# VierGewinnt010.net
KiCad netlist of a schematic drawn in EAGLE
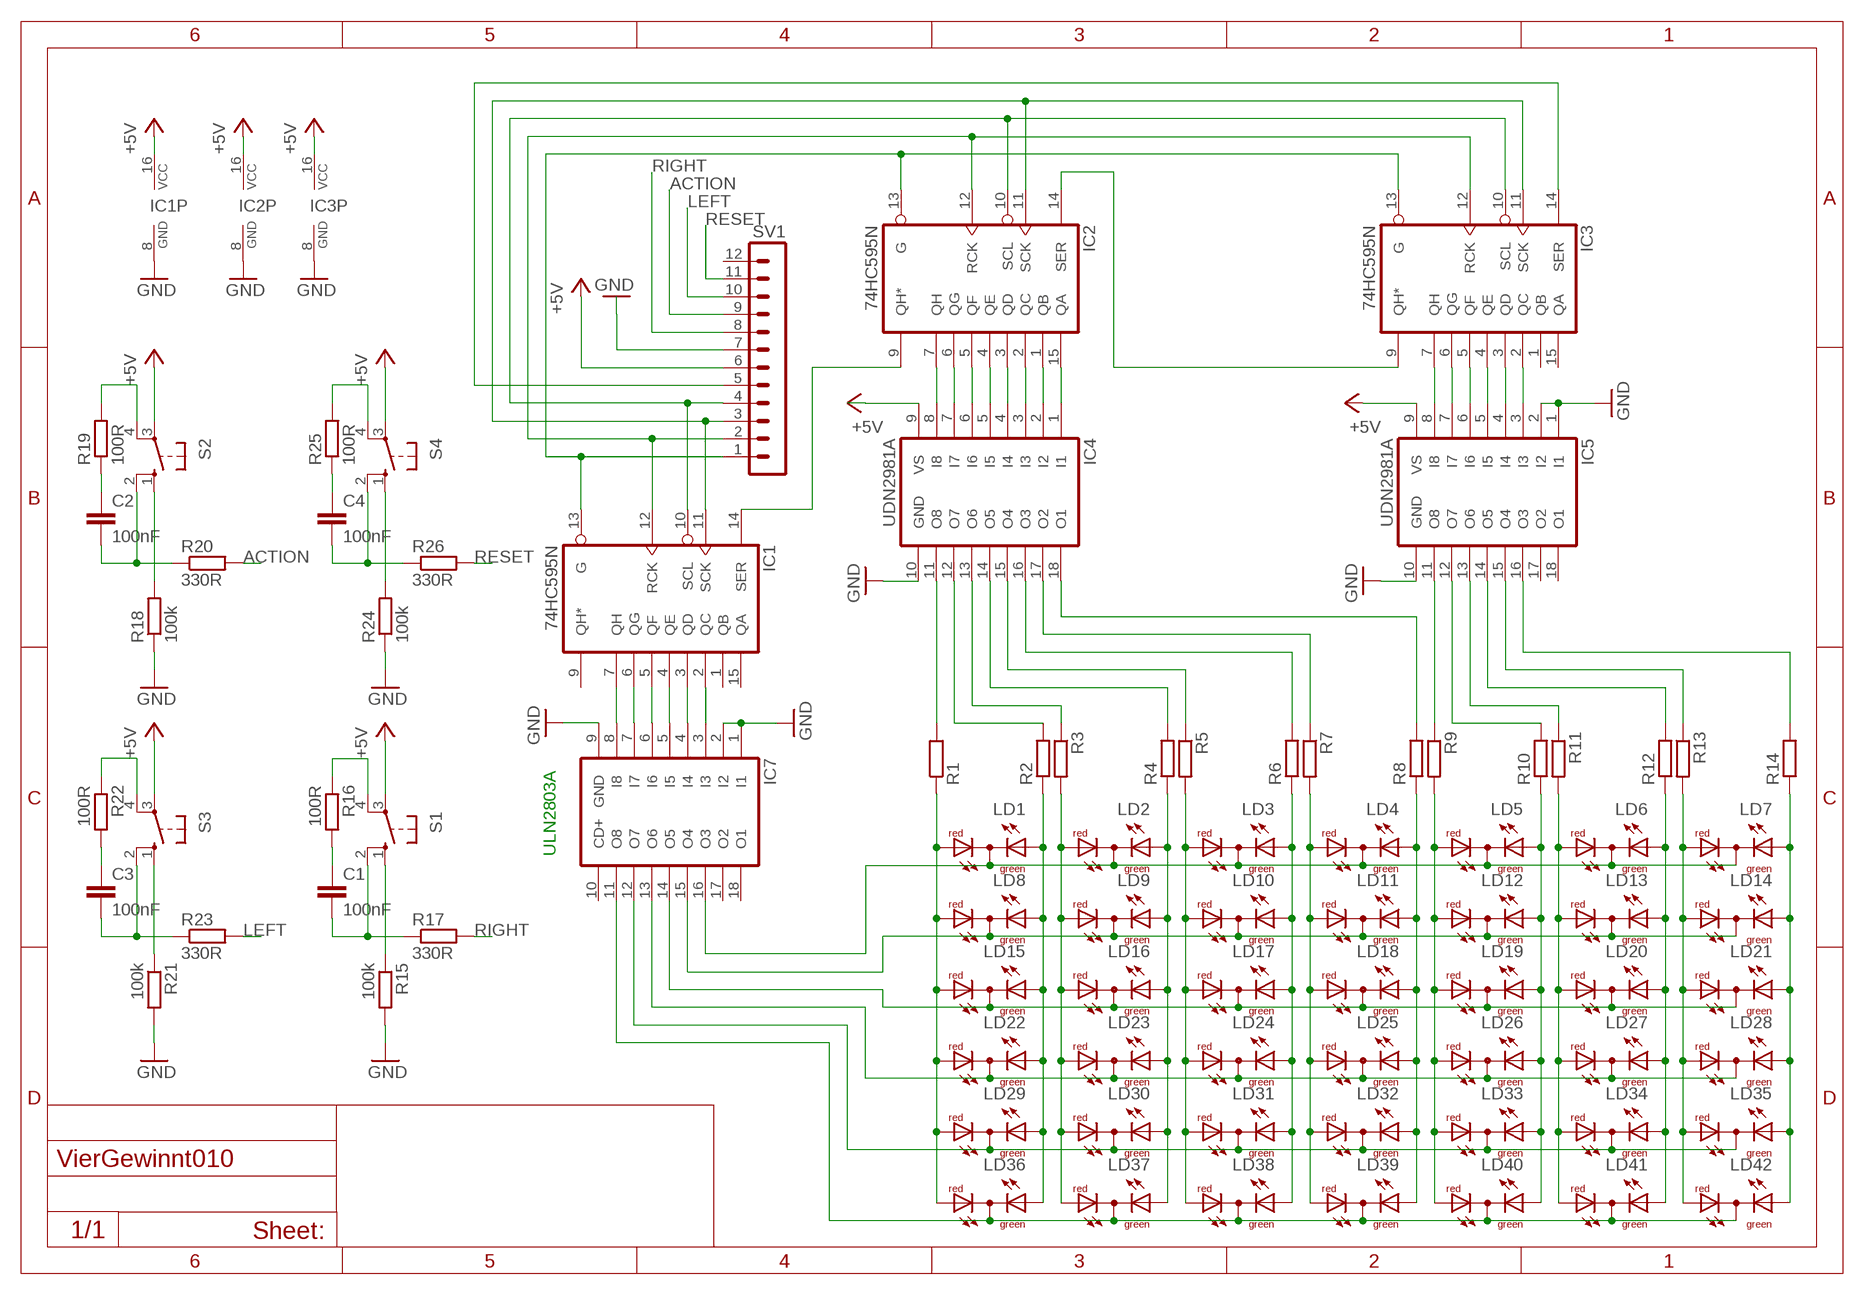
[diagram p0: schematic, sheet 1]

(export (version "E")
  (design (tool "Eeschema 10.0.6"))
  (components
    (comp (ref "C1")
      (value "100nF")
      (footprint "eagle-import:C0805")
      (libsource (lib "eagle-import") (part "C-EUC0805"))
    )
    (comp (ref "C2")
      (value "100nF")
      (footprint "eagle-import:C0805")
      (libsource (lib "eagle-import") (part "C-EUC0805"))
    )
    (comp (ref "C3")
      (value "100nF")
      (footprint "eagle-import:C0805")
      (libsource (lib "eagle-import") (part "C-EUC0805"))
    )
    (comp (ref "C4")
      (value "100nF")
      (footprint "eagle-import:C0805")
      (libsource (lib "eagle-import") (part "C-EUC0805"))
    )
    (comp (ref "IC1")
      (value "74HC595N")
      (footprint "eagle-import:DIL16")
      (libsource (lib "eagle-import") (part "74595NHC"))
    )
    (comp (ref "IC2")
      (value "74HC595N")
      (footprint "eagle-import:DIL16")
      (libsource (lib "eagle-import") (part "74595NHC"))
    )
    (comp (ref "IC3")
      (value "74HC595N")
      (footprint "eagle-import:DIL16")
      (libsource (lib "eagle-import") (part "74595NHC"))
    )
    (comp (ref "IC4")
      (value "UDN2981A")
      (footprint "eagle-import:DIL18")
      (libsource (lib "eagle-import") (part "UDN298A1"))
    )
    (comp (ref "IC5")
      (value "UDN2981A")
      (footprint "eagle-import:DIL18")
      (libsource (lib "eagle-import") (part "UDN298A1"))
    )
    (comp (ref "IC7")
      (value "ULN2803A")
      (footprint "eagle-import:DIL18")
      (libsource (lib "eagle-import") (part "ULN2803A"))
    )
    (comp (ref "LD1")
      (value "DUOLED-RG-C")
      (footprint "eagle-import:DUOLED-C-5MM")
      (libsource (lib "eagle-import") (part "DUOLED-RG-C"))
    )
    (comp (ref "LD2")
      (value "DUOLED-RG-C")
      (footprint "eagle-import:DUOLED-C-5MM")
      (libsource (lib "eagle-import") (part "DUOLED-RG-C"))
    )
    (comp (ref "LD3")
      (value "DUOLED-RG-C")
      (footprint "eagle-import:DUOLED-C-5MM")
      (libsource (lib "eagle-import") (part "DUOLED-RG-C"))
    )
    (comp (ref "LD4")
      (value "DUOLED-RG-C")
      (footprint "eagle-import:DUOLED-C-5MM")
      (libsource (lib "eagle-import") (part "DUOLED-RG-C"))
    )
    (comp (ref "LD5")
      (value "DUOLED-RG-C")
      (footprint "eagle-import:DUOLED-C-5MM")
      (libsource (lib "eagle-import") (part "DUOLED-RG-C"))
    )
    (comp (ref "LD6")
      (value "DUOLED-RG-C")
      (footprint "eagle-import:DUOLED-C-5MM")
      (libsource (lib "eagle-import") (part "DUOLED-RG-C"))
    )
    (comp (ref "LD7")
      (value "DUOLED-RG-C")
      (footprint "eagle-import:DUOLED-C-5MM")
      (libsource (lib "eagle-import") (part "DUOLED-RG-C"))
    )
    (comp (ref "LD8")
      (value "DUOLED-RG-C")
      (footprint "eagle-import:DUOLED-C-5MM")
      (libsource (lib "eagle-import") (part "DUOLED-RG-C"))
    )
    (comp (ref "LD9")
      (value "DUOLED-RG-C")
      (footprint "eagle-import:DUOLED-C-5MM")
      (libsource (lib "eagle-import") (part "DUOLED-RG-C"))
    )
    (comp (ref "LD10")
      (value "DUOLED-RG-C")
      (footprint "eagle-import:DUOLED-C-5MM")
      (libsource (lib "eagle-import") (part "DUOLED-RG-C"))
    )
    (comp (ref "LD11")
      (value "DUOLED-RG-C")
      (footprint "eagle-import:DUOLED-C-5MM")
      (libsource (lib "eagle-import") (part "DUOLED-RG-C"))
    )
    (comp (ref "LD12")
      (value "DUOLED-RG-C")
      (footprint "eagle-import:DUOLED-C-5MM")
      (libsource (lib "eagle-import") (part "DUOLED-RG-C"))
    )
    (comp (ref "LD13")
      (value "DUOLED-RG-C")
      (footprint "eagle-import:DUOLED-C-5MM")
      (libsource (lib "eagle-import") (part "DUOLED-RG-C"))
    )
    (comp (ref "LD14")
      (value "DUOLED-RG-C")
      (footprint "eagle-import:DUOLED-C-5MM")
      (libsource (lib "eagle-import") (part "DUOLED-RG-C"))
    )
    (comp (ref "LD15")
      (value "DUOLED-RG-C")
      (footprint "eagle-import:DUOLED-C-5MM")
      (libsource (lib "eagle-import") (part "DUOLED-RG-C"))
    )
    (comp (ref "LD16")
      (value "DUOLED-RG-C")
      (footprint "eagle-import:DUOLED-C-5MM")
      (libsource (lib "eagle-import") (part "DUOLED-RG-C"))
    )
    (comp (ref "LD17")
      (value "DUOLED-RG-C")
      (footprint "eagle-import:DUOLED-C-5MM")
      (libsource (lib "eagle-import") (part "DUOLED-RG-C"))
    )
    (comp (ref "LD18")
      (value "DUOLED-RG-C")
      (footprint "eagle-import:DUOLED-C-5MM")
      (libsource (lib "eagle-import") (part "DUOLED-RG-C"))
    )
    (comp (ref "LD19")
      (value "DUOLED-RG-C")
      (footprint "eagle-import:DUOLED-C-5MM")
      (libsource (lib "eagle-import") (part "DUOLED-RG-C"))
    )
    (comp (ref "LD20")
      (value "DUOLED-RG-C")
      (footprint "eagle-import:DUOLED-C-5MM")
      (libsource (lib "eagle-import") (part "DUOLED-RG-C"))
    )
    (comp (ref "LD21")
      (value "DUOLED-RG-C")
      (footprint "eagle-import:DUOLED-C-5MM")
      (libsource (lib "eagle-import") (part "DUOLED-RG-C"))
    )
    (comp (ref "LD22")
      (value "DUOLED-RG-C")
      (footprint "eagle-import:DUOLED-C-5MM")
      (libsource (lib "eagle-import") (part "DUOLED-RG-C"))
    )
    (comp (ref "LD23")
      (value "DUOLED-RG-C")
      (footprint "eagle-import:DUOLED-C-5MM")
      (libsource (lib "eagle-import") (part "DUOLED-RG-C"))
    )
    (comp (ref "LD24")
      (value "DUOLED-RG-C")
      (footprint "eagle-import:DUOLED-C-5MM")
      (libsource (lib "eagle-import") (part "DUOLED-RG-C"))
    )
    (comp (ref "LD25")
      (value "DUOLED-RG-C")
      (footprint "eagle-import:DUOLED-C-5MM")
      (libsource (lib "eagle-import") (part "DUOLED-RG-C"))
    )
    (comp (ref "LD26")
      (value "DUOLED-RG-C")
      (footprint "eagle-import:DUOLED-C-5MM")
      (libsource (lib "eagle-import") (part "DUOLED-RG-C"))
    )
    (comp (ref "LD27")
      (value "DUOLED-RG-C")
      (footprint "eagle-import:DUOLED-C-5MM")
      (libsource (lib "eagle-import") (part "DUOLED-RG-C"))
    )
    (comp (ref "LD28")
      (value "DUOLED-RG-C")
      (footprint "eagle-import:DUOLED-C-5MM")
      (libsource (lib "eagle-import") (part "DUOLED-RG-C"))
    )
    (comp (ref "LD29")
      (value "DUOLED-RG-C")
      (footprint "eagle-import:DUOLED-C-5MM")
      (libsource (lib "eagle-import") (part "DUOLED-RG-C"))
    )
    (comp (ref "LD30")
      (value "DUOLED-RG-C")
      (footprint "eagle-import:DUOLED-C-5MM")
      (libsource (lib "eagle-import") (part "DUOLED-RG-C"))
    )
    (comp (ref "LD31")
      (value "DUOLED-RG-C")
      (footprint "eagle-import:DUOLED-C-5MM")
      (libsource (lib "eagle-import") (part "DUOLED-RG-C"))
    )
    (comp (ref "LD32")
      (value "DUOLED-RG-C")
      (footprint "eagle-import:DUOLED-C-5MM")
      (libsource (lib "eagle-import") (part "DUOLED-RG-C"))
    )
    (comp (ref "LD33")
      (value "DUOLED-RG-C")
      (footprint "eagle-import:DUOLED-C-5MM")
      (libsource (lib "eagle-import") (part "DUOLED-RG-C"))
    )
    (comp (ref "LD34")
      (value "DUOLED-RG-C")
      (footprint "eagle-import:DUOLED-C-5MM")
      (libsource (lib "eagle-import") (part "DUOLED-RG-C"))
    )
    (comp (ref "LD35")
      (value "DUOLED-RG-C")
      (footprint "eagle-import:DUOLED-C-5MM")
      (libsource (lib "eagle-import") (part "DUOLED-RG-C"))
    )
    (comp (ref "LD36")
      (value "DUOLED-RG-C")
      (footprint "eagle-import:DUOLED-C-5MM")
      (libsource (lib "eagle-import") (part "DUOLED-RG-C"))
    )
    (comp (ref "LD37")
      (value "DUOLED-RG-C")
      (footprint "eagle-import:DUOLED-C-5MM")
      (libsource (lib "eagle-import") (part "DUOLED-RG-C"))
    )
    (comp (ref "LD38")
      (value "DUOLED-RG-C")
      (footprint "eagle-import:DUOLED-C-5MM")
      (libsource (lib "eagle-import") (part "DUOLED-RG-C"))
    )
    (comp (ref "LD39")
      (value "DUOLED-RG-C")
      (footprint "eagle-import:DUOLED-C-5MM")
      (libsource (lib "eagle-import") (part "DUOLED-RG-C"))
    )
    (comp (ref "LD40")
      (value "DUOLED-RG-C")
      (footprint "eagle-import:DUOLED-C-5MM")
      (libsource (lib "eagle-import") (part "DUOLED-RG-C"))
    )
    (comp (ref "LD41")
      (value "DUOLED-RG-C")
      (footprint "eagle-import:DUOLED-C-5MM")
      (libsource (lib "eagle-import") (part "DUOLED-RG-C"))
    )
    (comp (ref "LD42")
      (value "DUOLED-RG-C")
      (footprint "eagle-import:DUOLED-C-5MM")
      (libsource (lib "eagle-import") (part "DUOLED-RG-C"))
    )
    (comp (ref "R1")
      (value "R-EU_0207/10")
      (footprint "eagle-import:0207_10")
      (libsource (lib "eagle-import") (part "R-EU_0207/10"))
    )
    (comp (ref "R2")
      (value "R-EU_0207/10")
      (footprint "eagle-import:0207_10")
      (libsource (lib "eagle-import") (part "R-EU_0207/10"))
    )
    (comp (ref "R3")
      (value "R-EU_0207/10")
      (footprint "eagle-import:0207_10")
      (libsource (lib "eagle-import") (part "R-EU_0207/10"))
    )
    (comp (ref "R4")
      (value "R-EU_0207/10")
      (footprint "eagle-import:0207_10")
      (libsource (lib "eagle-import") (part "R-EU_0207/10"))
    )
    (comp (ref "R5")
      (value "R-EU_0207/10")
      (footprint "eagle-import:0207_10")
      (libsource (lib "eagle-import") (part "R-EU_0207/10"))
    )
    (comp (ref "R6")
      (value "R-EU_0207/10")
      (footprint "eagle-import:0207_10")
      (libsource (lib "eagle-import") (part "R-EU_0207/10"))
    )
    (comp (ref "R7")
      (value "R-EU_0207/10")
      (footprint "eagle-import:0207_10")
      (libsource (lib "eagle-import") (part "R-EU_0207/10"))
    )
    (comp (ref "R8")
      (value "R-EU_0207/10")
      (footprint "eagle-import:0207_10")
      (libsource (lib "eagle-import") (part "R-EU_0207/10"))
    )
    (comp (ref "R9")
      (value "R-EU_0207/10")
      (footprint "eagle-import:0207_10")
      (libsource (lib "eagle-import") (part "R-EU_0207/10"))
    )
    (comp (ref "R10")
      (value "R-EU_0207/10")
      (footprint "eagle-import:0207_10")
      (libsource (lib "eagle-import") (part "R-EU_0207/10"))
    )
    (comp (ref "R11")
      (value "R-EU_0207/10")
      (footprint "eagle-import:0207_10")
      (libsource (lib "eagle-import") (part "R-EU_0207/10"))
    )
    (comp (ref "R12")
      (value "R-EU_0207/10")
      (footprint "eagle-import:0207_10")
      (libsource (lib "eagle-import") (part "R-EU_0207/10"))
    )
    (comp (ref "R13")
      (value "R-EU_0207/10")
      (footprint "eagle-import:0207_10")
      (libsource (lib "eagle-import") (part "R-EU_0207/10"))
    )
    (comp (ref "R14")
      (value "R-EU_0207/10")
      (footprint "eagle-import:0207_10")
      (libsource (lib "eagle-import") (part "R-EU_0207/10"))
    )
    (comp (ref "R15")
      (value "100k")
      (footprint "eagle-import:R0603")
      (libsource (lib "eagle-import") (part "R-EU_R0603"))
    )
    (comp (ref "R16")
      (value "100R")
      (footprint "eagle-import:R0603")
      (libsource (lib "eagle-import") (part "R-EU_R0603"))
    )
    (comp (ref "R17")
      (value "330R")
      (footprint "eagle-import:R0603")
      (libsource (lib "eagle-import") (part "R-EU_R0603"))
    )
    (comp (ref "R18")
      (value "100k")
      (footprint "eagle-import:R0603")
      (libsource (lib "eagle-import") (part "R-EU_R0603"))
    )
    (comp (ref "R19")
      (value "100R")
      (footprint "eagle-import:R0603")
      (libsource (lib "eagle-import") (part "R-EU_R0603"))
    )
    (comp (ref "R20")
      (value "330R")
      (footprint "eagle-import:R0603")
      (libsource (lib "eagle-import") (part "R-EU_R0603"))
    )
    (comp (ref "R21")
      (value "100k")
      (footprint "eagle-import:R0603")
      (libsource (lib "eagle-import") (part "R-EU_R0603"))
    )
    (comp (ref "R22")
      (value "100R")
      (footprint "eagle-import:R0603")
      (libsource (lib "eagle-import") (part "R-EU_R0603"))
    )
    (comp (ref "R23")
      (value "330R")
      (footprint "eagle-import:R0603")
      (libsource (lib "eagle-import") (part "R-EU_R0603"))
    )
    (comp (ref "R24")
      (value "100k")
      (footprint "eagle-import:R0603")
      (libsource (lib "eagle-import") (part "R-EU_R0603"))
    )
    (comp (ref "R25")
      (value "100R")
      (footprint "eagle-import:R0603")
      (libsource (lib "eagle-import") (part "R-EU_R0603"))
    )
    (comp (ref "R26")
      (value "330R")
      (footprint "eagle-import:R0603")
      (libsource (lib "eagle-import") (part "R-EU_R0603"))
    )
    (comp (ref "S1")
      (value "10-XX")
      (footprint "eagle-import:B3F-10XX")
      (libsource (lib "eagle-import") (part "10-XX"))
    )
    (comp (ref "S2")
      (value "10-XX")
      (footprint "eagle-import:B3F-10XX")
      (libsource (lib "eagle-import") (part "10-XX"))
    )
    (comp (ref "S3")
      (value "10-XX")
      (footprint "eagle-import:B3F-10XX")
      (libsource (lib "eagle-import") (part "10-XX"))
    )
    (comp (ref "S4")
      (value "10-XX")
      (footprint "eagle-import:B3F-10XX")
      (libsource (lib "eagle-import") (part "10-XX"))
    )
    (comp (ref "SV1")
      (value "MA12-1")
      (footprint "eagle-import:MA12-1")
      (libsource (lib "eagle-import") (part "MA12-1"))
    )
  )
  (nets
    (net (code "1") (name "+5V") (class "Default")
      (node (ref "IC1") (pin "16") (pinfunction "VCC_16") (pintype "power_in"))
      (node (ref "IC2") (pin "16") (pinfunction "VCC_16") (pintype "power_in"))
      (node (ref "IC3") (pin "16") (pinfunction "VCC_16") (pintype "power_in"))
      (node (ref "IC4") (pin "9") (pinfunction "VS_9") (pintype "passive"))
      (node (ref "IC5") (pin "9") (pinfunction "VS_9") (pintype "passive"))
      (node (ref "S1") (pin "3") (pinfunction "P_3") (pintype "passive"))
      (node (ref "S2") (pin "3") (pinfunction "P_3") (pintype "passive"))
      (node (ref "S3") (pin "3") (pinfunction "P_3") (pintype "passive"))
      (node (ref "S4") (pin "3") (pinfunction "P_3") (pintype "passive"))
      (node (ref "SV1") (pin "6") (pinfunction "6_6") (pintype "passive"))
    )
    (net (code "2") (name "/ACTION") (class "Default")
      (node (ref "R20") (pin "2") (pinfunction "2_2") (pintype "passive"))
      (node (ref "SV1") (pin "9") (pinfunction "9_9") (pintype "passive"))
    )
    (net (code "3") (name "/LEFT") (class "Default")
      (node (ref "R23") (pin "2") (pinfunction "2_2") (pintype "passive"))
      (node (ref "SV1") (pin "10") (pinfunction "10_10") (pintype "passive"))
    )
    (net (code "4") (name "/RESET") (class "Default")
      (node (ref "R26") (pin "2") (pinfunction "2_2") (pintype "passive"))
      (node (ref "SV1") (pin "11") (pinfunction "11_11") (pintype "passive"))
    )
    (net (code "5") (name "/RIGHT") (class "Default")
      (node (ref "R17") (pin "2") (pinfunction "2_2") (pintype "passive"))
      (node (ref "SV1") (pin "8") (pinfunction "8_8") (pintype "passive"))
    )
    (net (code "6") (name "GND") (class "Default")
      (node (ref "IC1") (pin "8") (pinfunction "GND_8") (pintype "power_in"))
      (node (ref "IC2") (pin "8") (pinfunction "GND_8") (pintype "power_in"))
      (node (ref "IC3") (pin "8") (pinfunction "GND_8") (pintype "power_in"))
      (node (ref "IC4") (pin "10") (pinfunction "GND_10") (pintype "power_in"))
      (node (ref "IC5") (pin "1") (pinfunction "I1_1") (pintype "input"))
      (node (ref "IC5") (pin "10") (pinfunction "GND_10") (pintype "power_in"))
      (node (ref "IC5") (pin "2") (pinfunction "I2_2") (pintype "input"))
      (node (ref "IC7") (pin "1") (pinfunction "I1_1") (pintype "input"))
      (node (ref "IC7") (pin "2") (pinfunction "I2_2") (pintype "input"))
      (node (ref "IC7") (pin "9") (pinfunction "GND_9") (pintype "power_in"))
      (node (ref "R15") (pin "2") (pinfunction "2_2") (pintype "passive"))
      (node (ref "R18") (pin "1") (pinfunction "1_1") (pintype "passive"))
      (node (ref "R21") (pin "2") (pinfunction "2_2") (pintype "passive"))
      (node (ref "R24") (pin "1") (pinfunction "1_1") (pintype "passive"))
      (node (ref "SV1") (pin "7") (pinfunction "7_7") (pintype "passive"))
    )
    (net (code "7") (name "Net-(C1-Pad1)") (class "Default")
      (node (ref "C1") (pin "1") (pinfunction "1_1") (pintype "passive"))
      (node (ref "R16") (pin "2") (pinfunction "2_2") (pintype "passive"))
    )
    (net (code "8") (name "Net-(C2-Pad1)") (class "Default")
      (node (ref "C2") (pin "1") (pinfunction "1_1") (pintype "passive"))
      (node (ref "R19") (pin "1") (pinfunction "1_1") (pintype "passive"))
    )
    (net (code "9") (name "Net-(C3-Pad1)") (class "Default")
      (node (ref "C3") (pin "1") (pinfunction "1_1") (pintype "passive"))
      (node (ref "R22") (pin "2") (pinfunction "2_2") (pintype "passive"))
    )
    (net (code "10") (name "Net-(C4-Pad1)") (class "Default")
      (node (ref "C4") (pin "1") (pinfunction "1_1") (pintype "passive"))
      (node (ref "R25") (pin "1") (pinfunction "1_1") (pintype "passive"))
    )
    (net (code "11") (name "Net-(IC1A-G)") (class "Default")
      (node (ref "IC1") (pin "13") (pinfunction "G_13") (pintype "input"))
      (node (ref "IC2") (pin "13") (pinfunction "G_13") (pintype "input"))
      (node (ref "IC3") (pin "13") (pinfunction "G_13") (pintype "input"))
      (node (ref "SV1") (pin "1") (pinfunction "1_1") (pintype "passive"))
    )
    (net (code "12") (name "Net-(IC1A-QC)") (class "Default")
      (node (ref "IC1") (pin "2") (pinfunction "QC_2") (pintype "tri_state"))
      (node (ref "IC7") (pin "3") (pinfunction "I3_3") (pintype "input"))
    )
    (net (code "13") (name "Net-(IC1A-QD)") (class "Default")
      (node (ref "IC1") (pin "3") (pinfunction "QD_3") (pintype "tri_state"))
      (node (ref "IC7") (pin "4") (pinfunction "I4_4") (pintype "input"))
    )
    (net (code "14") (name "Net-(IC1A-QE)") (class "Default")
      (node (ref "IC1") (pin "4") (pinfunction "QE_4") (pintype "tri_state"))
      (node (ref "IC7") (pin "5") (pinfunction "I5_5") (pintype "input"))
    )
    (net (code "15") (name "Net-(IC1A-QF)") (class "Default")
      (node (ref "IC1") (pin "5") (pinfunction "QF_5") (pintype "tri_state"))
      (node (ref "IC7") (pin "6") (pinfunction "I6_6") (pintype "input"))
    )
    (net (code "16") (name "Net-(IC1A-QG)") (class "Default")
      (node (ref "IC1") (pin "6") (pinfunction "QG_6") (pintype "tri_state"))
      (node (ref "IC7") (pin "7") (pinfunction "I7_7") (pintype "input"))
    )
    (net (code "17") (name "Net-(IC1A-QH)") (class "Default")
      (node (ref "IC1") (pin "7") (pinfunction "QH_7") (pintype "tri_state"))
      (node (ref "IC7") (pin "8") (pinfunction "I8_8") (pintype "input"))
    )
    (net (code "18") (name "Net-(IC1A-RCK)") (class "Default")
      (node (ref "IC1") (pin "12") (pinfunction "RCK_12") (pintype "input"))
      (node (ref "IC2") (pin "12") (pinfunction "RCK_12") (pintype "input"))
      (node (ref "IC3") (pin "12") (pinfunction "RCK_12") (pintype "input"))
      (node (ref "SV1") (pin "2") (pinfunction "2_2") (pintype "passive"))
    )
    (net (code "19") (name "Net-(IC1A-SCK)") (class "Default")
      (node (ref "IC1") (pin "11") (pinfunction "SCK_11") (pintype "input"))
      (node (ref "IC2") (pin "11") (pinfunction "SCK_11") (pintype "input"))
      (node (ref "IC3") (pin "11") (pinfunction "SCK_11") (pintype "input"))
      (node (ref "SV1") (pin "3") (pinfunction "3_3") (pintype "passive"))
    )
    (net (code "20") (name "Net-(IC1A-SCL)") (class "Default")
      (node (ref "IC1") (pin "10") (pinfunction "SCL_10") (pintype "input"))
      (node (ref "IC2") (pin "10") (pinfunction "SCL_10") (pintype "input"))
      (node (ref "IC3") (pin "10") (pinfunction "SCL_10") (pintype "input"))
      (node (ref "SV1") (pin "4") (pinfunction "4_4") (pintype "passive"))
    )
    (net (code "21") (name "Net-(IC1A-SER)") (class "Default")
      (node (ref "IC1") (pin "14") (pinfunction "SER_14") (pintype "input"))
      (node (ref "IC2") (pin "9") (pinfunction "QH*_9") (pintype "tri_state"))
    )
    (net (code "22") (name "Net-(IC2A-QA)") (class "Default")
      (node (ref "IC2") (pin "15") (pinfunction "QA_15") (pintype "tri_state"))
      (node (ref "IC4") (pin "1") (pinfunction "I1_1") (pintype "input"))
    )
    (net (code "23") (name "Net-(IC2A-QB)") (class "Default")
      (node (ref "IC2") (pin "1") (pinfunction "QB_1") (pintype "tri_state"))
      (node (ref "IC4") (pin "2") (pinfunction "I2_2") (pintype "input"))
    )
    (net (code "24") (name "Net-(IC2A-QC)") (class "Default")
      (node (ref "IC2") (pin "2") (pinfunction "QC_2") (pintype "tri_state"))
      (node (ref "IC4") (pin "3") (pinfunction "I3_3") (pintype "input"))
    )
    (net (code "25") (name "Net-(IC2A-QD)") (class "Default")
      (node (ref "IC2") (pin "3") (pinfunction "QD_3") (pintype "tri_state"))
      (node (ref "IC4") (pin "4") (pinfunction "I4_4") (pintype "input"))
    )
    (net (code "26") (name "Net-(IC2A-QE)") (class "Default")
      (node (ref "IC2") (pin "4") (pinfunction "QE_4") (pintype "tri_state"))
      (node (ref "IC4") (pin "5") (pinfunction "I5_5") (pintype "input"))
    )
    (net (code "27") (name "Net-(IC2A-QF)") (class "Default")
      (node (ref "IC2") (pin "5") (pinfunction "QF_5") (pintype "tri_state"))
      (node (ref "IC4") (pin "6") (pinfunction "I6_6") (pintype "input"))
    )
    (net (code "28") (name "Net-(IC2A-QG)") (class "Default")
      (node (ref "IC2") (pin "6") (pinfunction "QG_6") (pintype "tri_state"))
      (node (ref "IC4") (pin "7") (pinfunction "I7_7") (pintype "input"))
    )
    (net (code "29") (name "Net-(IC2A-QH)") (class "Default")
      (node (ref "IC2") (pin "7") (pinfunction "QH_7") (pintype "tri_state"))
      (node (ref "IC4") (pin "8") (pinfunction "I8_8") (pintype "input"))
    )
    (net (code "30") (name "Net-(IC2A-SER)") (class "Default")
      (node (ref "IC2") (pin "14") (pinfunction "SER_14") (pintype "input"))
      (node (ref "IC3") (pin "9") (pinfunction "QH*_9") (pintype "tri_state"))
    )
    (net (code "31") (name "Net-(IC3A-QC)") (class "Default")
      (node (ref "IC3") (pin "2") (pinfunction "QC_2") (pintype "tri_state"))
      (node (ref "IC5") (pin "3") (pinfunction "I3_3") (pintype "input"))
    )
    (net (code "32") (name "Net-(IC3A-QD)") (class "Default")
      (node (ref "IC3") (pin "3") (pinfunction "QD_3") (pintype "tri_state"))
      (node (ref "IC5") (pin "4") (pinfunction "I4_4") (pintype "input"))
    )
    (net (code "33") (name "Net-(IC3A-QE)") (class "Default")
      (node (ref "IC3") (pin "4") (pinfunction "QE_4") (pintype "tri_state"))
      (node (ref "IC5") (pin "5") (pinfunction "I5_5") (pintype "input"))
    )
    (net (code "34") (name "Net-(IC3A-QF)") (class "Default")
      (node (ref "IC3") (pin "5") (pinfunction "QF_5") (pintype "tri_state"))
      (node (ref "IC5") (pin "6") (pinfunction "I6_6") (pintype "input"))
    )
    (net (code "35") (name "Net-(IC3A-QG)") (class "Default")
      (node (ref "IC3") (pin "6") (pinfunction "QG_6") (pintype "tri_state"))
      (node (ref "IC5") (pin "7") (pinfunction "I7_7") (pintype "input"))
    )
    (net (code "36") (name "Net-(IC3A-QH)") (class "Default")
      (node (ref "IC3") (pin "7") (pinfunction "QH_7") (pintype "tri_state"))
      (node (ref "IC5") (pin "8") (pinfunction "I8_8") (pintype "input"))
    )
    (net (code "37") (name "Net-(IC3A-SER)") (class "Default")
      (node (ref "IC3") (pin "14") (pinfunction "SER_14") (pintype "input"))
      (node (ref "SV1") (pin "5") (pinfunction "5_5") (pintype "passive"))
    )
    (net (code "38") (name "Net-(IC4-O1)") (class "Default")
      (node (ref "IC4") (pin "18") (pinfunction "O1_18") (pintype "open_collector"))
      (node (ref "R8") (pin "2") (pinfunction "2_2") (pintype "passive"))
    )
    (net (code "39") (name "Net-(IC4-O2)") (class "Default")
      (node (ref "IC4") (pin "17") (pinfunction "O2_17") (pintype "open_collector"))
      (node (ref "R7") (pin "1") (pinfunction "1_1") (pintype "passive"))
    )
    (net (code "40") (name "Net-(IC4-O3)") (class "Default")
      (node (ref "IC4") (pin "16") (pinfunction "O3_16") (pintype "open_collector"))
      (node (ref "R6") (pin "2") (pinfunction "2_2") (pintype "passive"))
    )
    (net (code "41") (name "Net-(IC4-O4)") (class "Default")
      (node (ref "IC4") (pin "15") (pinfunction "O4_15") (pintype "open_collector"))
      (node (ref "R5") (pin "1") (pinfunction "1_1") (pintype "passive"))
    )
    (net (code "42") (name "Net-(IC4-O5)") (class "Default")
      (node (ref "IC4") (pin "14") (pinfunction "O5_14") (pintype "open_collector"))
      (node (ref "R4") (pin "2") (pinfunction "2_2") (pintype "passive"))
    )
    (net (code "43") (name "Net-(IC4-O6)") (class "Default")
      (node (ref "IC4") (pin "13") (pinfunction "O6_13") (pintype "open_collector"))
      (node (ref "R3") (pin "1") (pinfunction "1_1") (pintype "passive"))
    )
    (net (code "44") (name "Net-(IC4-O7)") (class "Default")
      (node (ref "IC4") (pin "12") (pinfunction "O7_12") (pintype "open_collector"))
      (node (ref "R2") (pin "2") (pinfunction "2_2") (pintype "passive"))
    )
    (net (code "45") (name "Net-(IC4-O8)") (class "Default")
      (node (ref "IC4") (pin "11") (pinfunction "O8_11") (pintype "open_collector"))
      (node (ref "R1") (pin "2") (pinfunction "2_2") (pintype "passive"))
    )
    (net (code "46") (name "Net-(IC5-O3)") (class "Default")
      (node (ref "IC5") (pin "16") (pinfunction "O3_16") (pintype "open_collector"))
      (node (ref "R14") (pin "2") (pinfunction "2_2") (pintype "passive"))
    )
    (net (code "47") (name "Net-(IC5-O4)") (class "Default")
      (node (ref "IC5") (pin "15") (pinfunction "O4_15") (pintype "open_collector"))
      (node (ref "R13") (pin "1") (pinfunction "1_1") (pintype "passive"))
    )
    (net (code "48") (name "Net-(IC5-O5)") (class "Default")
      (node (ref "IC5") (pin "14") (pinfunction "O5_14") (pintype "open_collector"))
      (node (ref "R12") (pin "2") (pinfunction "2_2") (pintype "passive"))
    )
    (net (code "49") (name "Net-(IC5-O6)") (class "Default")
      (node (ref "IC5") (pin "13") (pinfunction "O6_13") (pintype "open_collector"))
      (node (ref "R11") (pin "1") (pinfunction "1_1") (pintype "passive"))
    )
    (net (code "50") (name "Net-(IC5-O7)") (class "Default")
      (node (ref "IC5") (pin "12") (pinfunction "O7_12") (pintype "open_collector"))
      (node (ref "R10") (pin "2") (pinfunction "2_2") (pintype "passive"))
    )
    (net (code "51") (name "Net-(IC5-O8)") (class "Default")
      (node (ref "IC5") (pin "11") (pinfunction "O8_11") (pintype "open_collector"))
      (node (ref "R9") (pin "1") (pinfunction "1_1") (pintype "passive"))
    )
    (net (code "52") (name "Net-(IC7-O3)") (class "Default")
      (node (ref "IC7") (pin "16") (pinfunction "O3_16") (pintype "open_collector"))
      (node (ref "LD1") (pin "C") (pinfunction "C_C") (pintype "passive"))
      (node (ref "LD2") (pin "C") (pinfunction "C_C") (pintype "passive"))
      (node (ref "LD3") (pin "C") (pinfunction "C_C") (pintype "passive"))
      (node (ref "LD4") (pin "C") (pinfunction "C_C") (pintype "passive"))
      (node (ref "LD5") (pin "C") (pinfunction "C_C") (pintype "passive"))
      (node (ref "LD6") (pin "C") (pinfunction "C_C") (pintype "passive"))
      (node (ref "LD7") (pin "C") (pinfunction "C_C") (pintype "passive"))
    )
    (net (code "53") (name "Net-(IC7-O4)") (class "Default")
      (node (ref "IC7") (pin "15") (pinfunction "O4_15") (pintype "open_collector"))
      (node (ref "LD10") (pin "C") (pinfunction "C_C") (pintype "passive"))
      (node (ref "LD11") (pin "C") (pinfunction "C_C") (pintype "passive"))
      (node (ref "LD12") (pin "C") (pinfunction "C_C") (pintype "passive"))
      (node (ref "LD13") (pin "C") (pinfunction "C_C") (pintype "passive"))
      (node (ref "LD14") (pin "C") (pinfunction "C_C") (pintype "passive"))
      (node (ref "LD8") (pin "C") (pinfunction "C_C") (pintype "passive"))
      (node (ref "LD9") (pin "C") (pinfunction "C_C") (pintype "passive"))
    )
    (net (code "54") (name "Net-(IC7-O5)") (class "Default")
      (node (ref "IC7") (pin "14") (pinfunction "O5_14") (pintype "open_collector"))
      (node (ref "LD15") (pin "C") (pinfunction "C_C") (pintype "passive"))
      (node (ref "LD16") (pin "C") (pinfunction "C_C") (pintype "passive"))
      (node (ref "LD17") (pin "C") (pinfunction "C_C") (pintype "passive"))
      (node (ref "LD18") (pin "C") (pinfunction "C_C") (pintype "passive"))
      (node (ref "LD19") (pin "C") (pinfunction "C_C") (pintype "passive"))
      (node (ref "LD20") (pin "C") (pinfunction "C_C") (pintype "passive"))
      (node (ref "LD21") (pin "C") (pinfunction "C_C") (pintype "passive"))
    )
    (net (code "55") (name "Net-(IC7-O6)") (class "Default")
      (node (ref "IC7") (pin "13") (pinfunction "O6_13") (pintype "open_collector"))
      (node (ref "LD22") (pin "C") (pinfunction "C_C") (pintype "passive"))
      (node (ref "LD23") (pin "C") (pinfunction "C_C") (pintype "passive"))
      (node (ref "LD24") (pin "C") (pinfunction "C_C") (pintype "passive"))
      (node (ref "LD25") (pin "C") (pinfunction "C_C") (pintype "passive"))
      (node (ref "LD26") (pin "C") (pinfunction "C_C") (pintype "passive"))
      (node (ref "LD27") (pin "C") (pinfunction "C_C") (pintype "passive"))
      (node (ref "LD28") (pin "C") (pinfunction "C_C") (pintype "passive"))
    )
    (net (code "56") (name "Net-(IC7-O7)") (class "Default")
      (node (ref "IC7") (pin "12") (pinfunction "O7_12") (pintype "open_collector"))
      (node (ref "LD29") (pin "C") (pinfunction "C_C") (pintype "passive"))
      (node (ref "LD30") (pin "C") (pinfunction "C_C") (pintype "passive"))
      (node (ref "LD31") (pin "C") (pinfunction "C_C") (pintype "passive"))
      (node (ref "LD32") (pin "C") (pinfunction "C_C") (pintype "passive"))
      (node (ref "LD33") (pin "C") (pinfunction "C_C") (pintype "passive"))
      (node (ref "LD34") (pin "C") (pinfunction "C_C") (pintype "passive"))
      (node (ref "LD35") (pin "C") (pinfunction "C_C") (pintype "passive"))
    )
    (net (code "57") (name "Net-(IC7-O8)") (class "Default")
      (node (ref "IC7") (pin "11") (pinfunction "O8_11") (pintype "open_collector"))
      (node (ref "LD36") (pin "C") (pinfunction "C_C") (pintype "passive"))
      (node (ref "LD37") (pin "C") (pinfunction "C_C") (pintype "passive"))
      (node (ref "LD38") (pin "C") (pinfunction "C_C") (pintype "passive"))
      (node (ref "LD39") (pin "C") (pinfunction "C_C") (pintype "passive"))
      (node (ref "LD40") (pin "C") (pinfunction "C_C") (pintype "passive"))
      (node (ref "LD41") (pin "C") (pinfunction "C_C") (pintype "passive"))
      (node (ref "LD42") (pin "C") (pinfunction "C_C") (pintype "passive"))
    )
    (net (code "58") (name "Net-(LD1-AG)") (class "Default")
      (node (ref "LD1") (pin "AX") (pinfunction "AG_AX") (pintype "passive"))
      (node (ref "LD15") (pin "AX") (pinfunction "AG_AX") (pintype "passive"))
      (node (ref "LD22") (pin "AX") (pinfunction "AG_AX") (pintype "passive"))
      (node (ref "LD29") (pin "AX") (pinfunction "AG_AX") (pintype "passive"))
      (node (ref "LD36") (pin "AX") (pinfunction "AG_AX") (pintype "passive"))
      (node (ref "LD8") (pin "AX") (pinfunction "AG_AX") (pintype "passive"))
      (node (ref "R2") (pin "1") (pinfunction "1_1") (pintype "passive"))
    )
    (net (code "59") (name "Net-(LD1-PadAR)") (class "Default")
      (node (ref "LD1") (pin "AR") (pinfunction "AR_AR") (pintype "passive"))
      (node (ref "LD15") (pin "AR") (pinfunction "AR_AR") (pintype "passive"))
      (node (ref "LD22") (pin "AR") (pinfunction "AR_AR") (pintype "passive"))
      (node (ref "LD29") (pin "AR") (pinfunction "AR_AR") (pintype "passive"))
      (node (ref "LD36") (pin "AR") (pinfunction "AR_AR") (pintype "passive"))
      (node (ref "LD8") (pin "AR") (pinfunction "AR_AR") (pintype "passive"))
      (node (ref "R1") (pin "1") (pinfunction "1_1") (pintype "passive"))
    )
    (net (code "60") (name "Net-(LD10-AG)") (class "Default")
      (node (ref "LD10") (pin "AX") (pinfunction "AG_AX") (pintype "passive"))
      (node (ref "LD17") (pin "AX") (pinfunction "AG_AX") (pintype "passive"))
      (node (ref "LD24") (pin "AX") (pinfunction "AG_AX") (pintype "passive"))
      (node (ref "LD3") (pin "AX") (pinfunction "AG_AX") (pintype "passive"))
      (node (ref "LD31") (pin "AX") (pinfunction "AG_AX") (pintype "passive"))
      (node (ref "LD38") (pin "AX") (pinfunction "AG_AX") (pintype "passive"))
      (node (ref "R6") (pin "1") (pinfunction "1_1") (pintype "passive"))
    )
    (net (code "61") (name "Net-(LD10-PadAR)") (class "Default")
      (node (ref "LD10") (pin "AR") (pinfunction "AR_AR") (pintype "passive"))
      (node (ref "LD17") (pin "AR") (pinfunction "AR_AR") (pintype "passive"))
      (node (ref "LD24") (pin "AR") (pinfunction "AR_AR") (pintype "passive"))
      (node (ref "LD3") (pin "AR") (pinfunction "AR_AR") (pintype "passive"))
      (node (ref "LD31") (pin "AR") (pinfunction "AR_AR") (pintype "passive"))
      (node (ref "LD38") (pin "AR") (pinfunction "AR_AR") (pintype "passive"))
      (node (ref "R5") (pin "2") (pinfunction "2_2") (pintype "passive"))
    )
    (net (code "62") (name "Net-(LD11-AG)") (class "Default")
      (node (ref "LD11") (pin "AX") (pinfunction "AG_AX") (pintype "passive"))
      (node (ref "LD18") (pin "AX") (pinfunction "AG_AX") (pintype "passive"))
      (node (ref "LD25") (pin "AX") (pinfunction "AG_AX") (pintype "passive"))
      (node (ref "LD32") (pin "AX") (pinfunction "AG_AX") (pintype "passive"))
      (node (ref "LD39") (pin "AX") (pinfunction "AG_AX") (pintype "passive"))
      (node (ref "LD4") (pin "AX") (pinfunction "AG_AX") (pintype "passive"))
      (node (ref "R8") (pin "1") (pinfunction "1_1") (pintype "passive"))
    )
    (net (code "63") (name "Net-(LD11-PadAR)") (class "Default")
      (node (ref "LD11") (pin "AR") (pinfunction "AR_AR") (pintype "passive"))
      (node (ref "LD18") (pin "AR") (pinfunction "AR_AR") (pintype "passive"))
      (node (ref "LD25") (pin "AR") (pinfunction "AR_AR") (pintype "passive"))
      (node (ref "LD32") (pin "AR") (pinfunction "AR_AR") (pintype "passive"))
      (node (ref "LD39") (pin "AR") (pinfunction "AR_AR") (pintype "passive"))
      (node (ref "LD4") (pin "AR") (pinfunction "AR_AR") (pintype "passive"))
      (node (ref "R7") (pin "2") (pinfunction "2_2") (pintype "passive"))
    )
    (net (code "64") (name "Net-(LD12-AG)") (class "Default")
      (node (ref "LD12") (pin "AX") (pinfunction "AG_AX") (pintype "passive"))
      (node (ref "LD19") (pin "AX") (pinfunction "AG_AX") (pintype "passive"))
      (node (ref "LD26") (pin "AX") (pinfunction "AG_AX") (pintype "passive"))
      (node (ref "LD33") (pin "AX") (pinfunction "AG_AX") (pintype "passive"))
      (node (ref "LD40") (pin "AX") (pinfunction "AG_AX") (pintype "passive"))
      (node (ref "LD5") (pin "AX") (pinfunction "AG_AX") (pintype "passive"))
      (node (ref "R10") (pin "1") (pinfunction "1_1") (pintype "passive"))
    )
    (net (code "65") (name "Net-(LD12-PadAR)") (class "Default")
      (node (ref "LD12") (pin "AR") (pinfunction "AR_AR") (pintype "passive"))
      (node (ref "LD19") (pin "AR") (pinfunction "AR_AR") (pintype "passive"))
      (node (ref "LD26") (pin "AR") (pinfunction "AR_AR") (pintype "passive"))
      (node (ref "LD33") (pin "AR") (pinfunction "AR_AR") (pintype "passive"))
      (node (ref "LD40") (pin "AR") (pinfunction "AR_AR") (pintype "passive"))
      (node (ref "LD5") (pin "AR") (pinfunction "AR_AR") (pintype "passive"))
      (node (ref "R9") (pin "2") (pinfunction "2_2") (pintype "passive"))
    )
    (net (code "66") (name "Net-(LD13-AG)") (class "Default")
      (node (ref "LD13") (pin "AX") (pinfunction "AG_AX") (pintype "passive"))
      (node (ref "LD20") (pin "AX") (pinfunction "AG_AX") (pintype "passive"))
      (node (ref "LD27") (pin "AX") (pinfunction "AG_AX") (pintype "passive"))
      (node (ref "LD34") (pin "AX") (pinfunction "AG_AX") (pintype "passive"))
      (node (ref "LD41") (pin "AX") (pinfunction "AG_AX") (pintype "passive"))
      (node (ref "LD6") (pin "AX") (pinfunction "AG_AX") (pintype "passive"))
      (node (ref "R12") (pin "1") (pinfunction "1_1") (pintype "passive"))
    )
    (net (code "67") (name "Net-(LD13-PadAR)") (class "Default")
      (node (ref "LD13") (pin "AR") (pinfunction "AR_AR") (pintype "passive"))
      (node (ref "LD20") (pin "AR") (pinfunction "AR_AR") (pintype "passive"))
      (node (ref "LD27") (pin "AR") (pinfunction "AR_AR") (pintype "passive"))
      (node (ref "LD34") (pin "AR") (pinfunction "AR_AR") (pintype "passive"))
      (node (ref "LD41") (pin "AR") (pinfunction "AR_AR") (pintype "passive"))
      (node (ref "LD6") (pin "AR") (pinfunction "AR_AR") (pintype "passive"))
      (node (ref "R11") (pin "2") (pinfunction "2_2") (pintype "passive"))
    )
    (net (code "68") (name "Net-(LD14-AG)") (class "Default")
      (node (ref "LD14") (pin "AX") (pinfunction "AG_AX") (pintype "passive"))
      (node (ref "LD21") (pin "AX") (pinfunction "AG_AX") (pintype "passive"))
      (node (ref "LD28") (pin "AX") (pinfunction "AG_AX") (pintype "passive"))
      (node (ref "LD35") (pin "AX") (pinfunction "AG_AX") (pintype "passive"))
      (node (ref "LD42") (pin "AX") (pinfunction "AG_AX") (pintype "passive"))
      (node (ref "LD7") (pin "AX") (pinfunction "AG_AX") (pintype "passive"))
      (node (ref "R14") (pin "1") (pinfunction "1_1") (pintype "passive"))
    )
    (net (code "69") (name "Net-(LD14-PadAR)") (class "Default")
      (node (ref "LD14") (pin "AR") (pinfunction "AR_AR") (pintype "passive"))
      (node (ref "LD21") (pin "AR") (pinfunction "AR_AR") (pintype "passive"))
      (node (ref "LD28") (pin "AR") (pinfunction "AR_AR") (pintype "passive"))
      (node (ref "LD35") (pin "AR") (pinfunction "AR_AR") (pintype "passive"))
      (node (ref "LD42") (pin "AR") (pinfunction "AR_AR") (pintype "passive"))
      (node (ref "LD7") (pin "AR") (pinfunction "AR_AR") (pintype "passive"))
      (node (ref "R13") (pin "2") (pinfunction "2_2") (pintype "passive"))
    )
    (net (code "70") (name "Net-(LD16-AG)") (class "Default")
      (node (ref "LD16") (pin "AX") (pinfunction "AG_AX") (pintype "passive"))
      (node (ref "LD2") (pin "AX") (pinfunction "AG_AX") (pintype "passive"))
      (node (ref "LD23") (pin "AX") (pinfunction "AG_AX") (pintype "passive"))
      (node (ref "LD30") (pin "AX") (pinfunction "AG_AX") (pintype "passive"))
      (node (ref "LD37") (pin "AX") (pinfunction "AG_AX") (pintype "passive"))
      (node (ref "LD9") (pin "AX") (pinfunction "AG_AX") (pintype "passive"))
      (node (ref "R4") (pin "1") (pinfunction "1_1") (pintype "passive"))
    )
    (net (code "71") (name "Net-(LD16-PadAR)") (class "Default")
      (node (ref "LD16") (pin "AR") (pinfunction "AR_AR") (pintype "passive"))
      (node (ref "LD2") (pin "AR") (pinfunction "AR_AR") (pintype "passive"))
      (node (ref "LD23") (pin "AR") (pinfunction "AR_AR") (pintype "passive"))
      (node (ref "LD30") (pin "AR") (pinfunction "AR_AR") (pintype "passive"))
      (node (ref "LD37") (pin "AR") (pinfunction "AR_AR") (pintype "passive"))
      (node (ref "LD9") (pin "AR") (pinfunction "AR_AR") (pintype "passive"))
      (node (ref "R3") (pin "2") (pinfunction "2_2") (pintype "passive"))
    )
    (net (code "72") (name "Net-(S1-P1)") (class "Default")
      (node (ref "R16") (pin "1") (pinfunction "1_1") (pintype "passive"))
      (node (ref "S1") (pin "4") (pinfunction "P1_4") (pintype "passive"))
    )
    (net (code "73") (name "Net-(S1-S)") (class "Default")
      (node (ref "R15") (pin "1") (pinfunction "1_1") (pintype "passive"))
      (node (ref "S1") (pin "1") (pinfunction "S_1") (pintype "passive"))
    )
    (net (code "74") (name "Net-(S1-S1)") (class "Default")
      (node (ref "C1") (pin "2") (pinfunction "2_2") (pintype "passive"))
      (node (ref "R17") (pin "1") (pinfunction "1_1") (pintype "passive"))
      (node (ref "S1") (pin "2") (pinfunction "S1_2") (pintype "passive"))
    )
    (net (code "75") (name "Net-(S2-P1)") (class "Default")
      (node (ref "R19") (pin "2") (pinfunction "2_2") (pintype "passive"))
      (node (ref "S2") (pin "4") (pinfunction "P1_4") (pintype "passive"))
    )
    (net (code "76") (name "Net-(S2-S)") (class "Default")
      (node (ref "R18") (pin "2") (pinfunction "2_2") (pintype "passive"))
      (node (ref "S2") (pin "1") (pinfunction "S_1") (pintype "passive"))
    )
    (net (code "77") (name "Net-(S2-S1)") (class "Default")
      (node (ref "C2") (pin "2") (pinfunction "2_2") (pintype "passive"))
      (node (ref "R20") (pin "1") (pinfunction "1_1") (pintype "passive"))
      (node (ref "S2") (pin "2") (pinfunction "S1_2") (pintype "passive"))
    )
    (net (code "78") (name "Net-(S3-P1)") (class "Default")
      (node (ref "R22") (pin "1") (pinfunction "1_1") (pintype "passive"))
      (node (ref "S3") (pin "4") (pinfunction "P1_4") (pintype "passive"))
    )
    (net (code "79") (name "Net-(S3-S)") (class "Default")
      (node (ref "R21") (pin "1") (pinfunction "1_1") (pintype "passive"))
      (node (ref "S3") (pin "1") (pinfunction "S_1") (pintype "passive"))
    )
    (net (code "80") (name "Net-(S3-S1)") (class "Default")
      (node (ref "C3") (pin "2") (pinfunction "2_2") (pintype "passive"))
      (node (ref "R23") (pin "1") (pinfunction "1_1") (pintype "passive"))
      (node (ref "S3") (pin "2") (pinfunction "S1_2") (pintype "passive"))
    )
    (net (code "81") (name "Net-(S4-P1)") (class "Default")
      (node (ref "R25") (pin "2") (pinfunction "2_2") (pintype "passive"))
      (node (ref "S4") (pin "4") (pinfunction "P1_4") (pintype "passive"))
    )
    (net (code "82") (name "Net-(S4-S)") (class "Default")
      (node (ref "R24") (pin "2") (pinfunction "2_2") (pintype "passive"))
      (node (ref "S4") (pin "1") (pinfunction "S_1") (pintype "passive"))
    )
    (net (code "83") (name "Net-(S4-S1)") (class "Default")
      (node (ref "C4") (pin "2") (pinfunction "2_2") (pintype "passive"))
      (node (ref "R26") (pin "1") (pinfunction "1_1") (pintype "passive"))
      (node (ref "S4") (pin "2") (pinfunction "S1_2") (pintype "passive"))
    )
    (net (code "84") (name "unconnected-(IC1A-QA-Pad15)") (class "Default")
      (node (ref "IC1") (pin "15") (pinfunction "QA_15") (pintype "tri_state"))
    )
    (net (code "85") (name "unconnected-(IC1A-QB-Pad1)") (class "Default")
      (node (ref "IC1") (pin "1") (pinfunction "QB_1") (pintype "tri_state"))
    )
    (net (code "86") (name "unconnected-(IC1A-QH*-Pad9)") (class "Default")
      (node (ref "IC1") (pin "9") (pinfunction "QH*_9") (pintype "tri_state"))
    )
    (net (code "87") (name "unconnected-(IC3A-QA-Pad15)") (class "Default")
      (node (ref "IC3") (pin "15") (pinfunction "QA_15") (pintype "tri_state"))
    )
    (net (code "88") (name "unconnected-(IC3A-QB-Pad1)") (class "Default")
      (node (ref "IC3") (pin "1") (pinfunction "QB_1") (pintype "tri_state"))
    )
    (net (code "89") (name "unconnected-(IC5-O1-Pad18)") (class "Default")
      (node (ref "IC5") (pin "18") (pinfunction "O1_18") (pintype "open_collector"))
    )
    (net (code "90") (name "unconnected-(IC5-O2-Pad17)") (class "Default")
      (node (ref "IC5") (pin "17") (pinfunction "O2_17") (pintype "open_collector"))
    )
    (net (code "91") (name "unconnected-(IC7-CD+-Pad10)") (class "Default")
      (node (ref "IC7") (pin "10") (pinfunction "CD+_10") (pintype "passive"))
    )
    (net (code "92") (name "unconnected-(IC7-O1-Pad18)") (class "Default")
      (node (ref "IC7") (pin "18") (pinfunction "O1_18") (pintype "open_collector"))
    )
    (net (code "93") (name "unconnected-(IC7-O2-Pad17)") (class "Default")
      (node (ref "IC7") (pin "17") (pinfunction "O2_17") (pintype "open_collector"))
    )
    (net (code "94") (name "unconnected-(SV1-Pad12)") (class "Default")
      (node (ref "SV1") (pin "12") (pinfunction "12_12") (pintype "passive"))
    )
  )
)
